# receiver_v0_1.net
KiCad netlist of a schematic drawn in Altium Designer
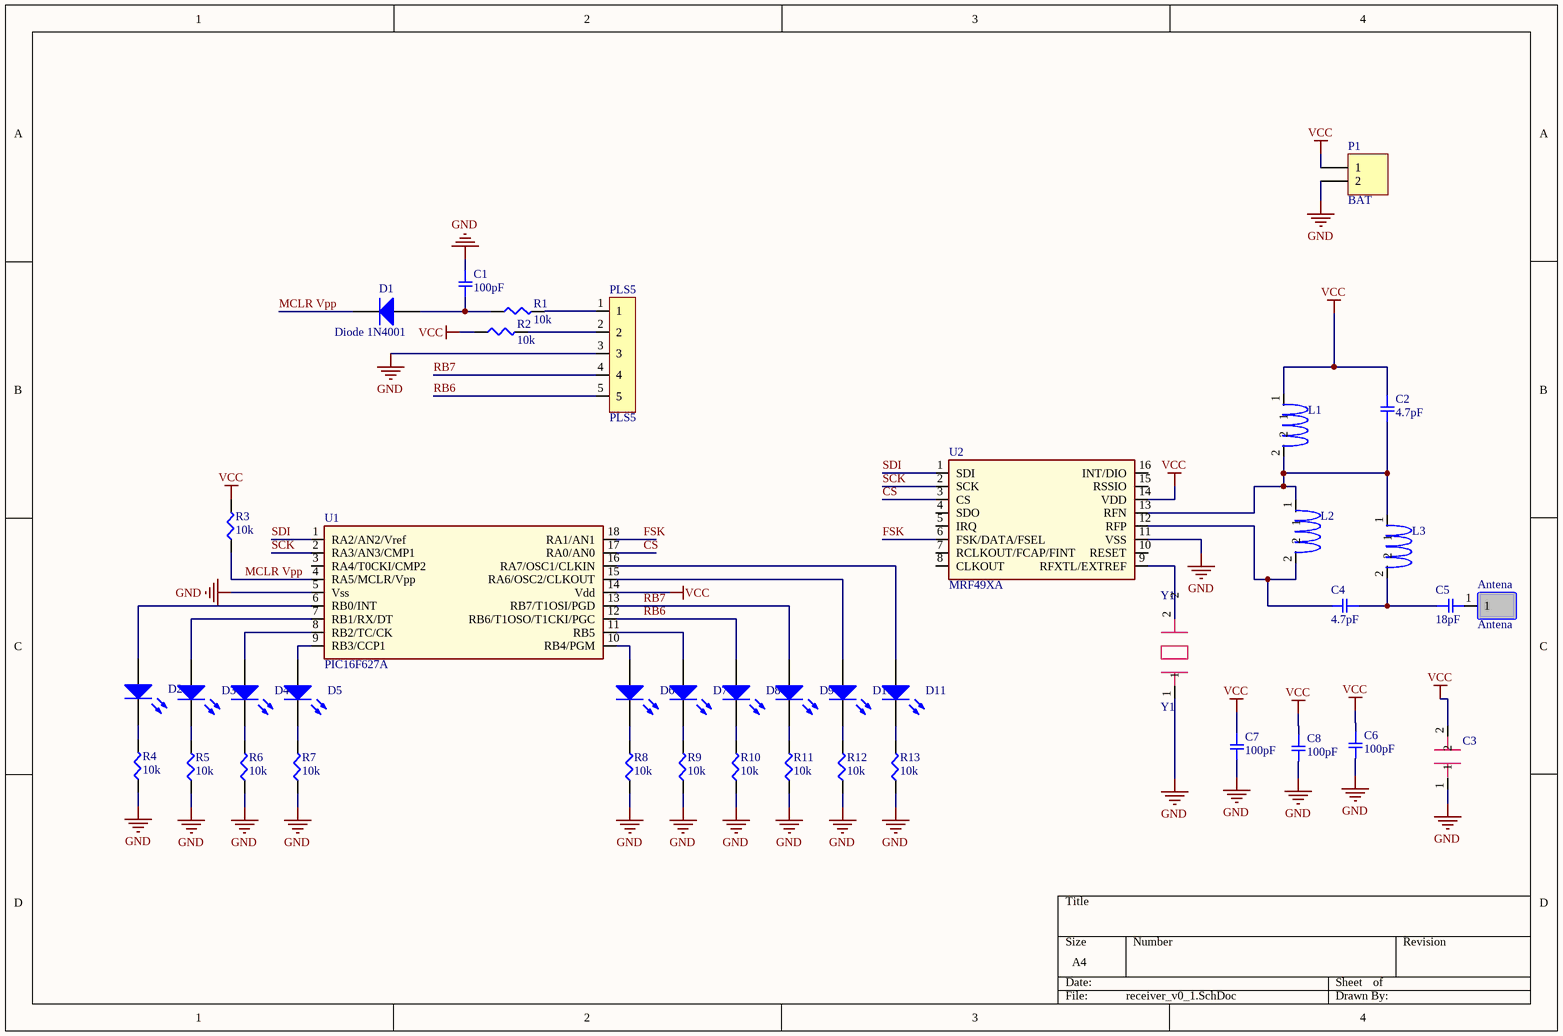
[diagram p0: receiver_v0_1.SchDoc]

(export (version "E")
  (design (tool "Eeschema 10.0.6"))
  (components
    (comp (ref "Antena") (value "Antena") (footprint "RCU:Anteny") (libsource (lib "RCU") (part "Antena")))
    (comp (ref "C1")
      (value "100pF")
      (footprint "SMD-1206C")
      (description "CAP CER 100PF 630V U2J 1206")
      (fields
        (field (name "DIGI-KEY PART NUMBER") "490-5043-1-ND")
        (field (name "PART NUMBER") "GCM31A7U2J101JX01D")
      )
      (libsource (lib "capacitor_murata_1206") (part "GCM31A7U2J101JX01D"))
    )
    (comp (ref "C2")
      (value "4.7pF")
      (footprint "SMD-0805C")
      (description "CAP CER 4.7PF 100V NP0 0805")
      (fields
        (field (name "DIGI-KEY PART NUMBER") "490-11278-1-ND")
        (field (name "PART NUMBER") "GQM2195C2A4R7BB01D")
      )
      (libsource (lib "capacitor_murata_0805") (part "GQM2195C2A4R7BB01D"))
    )
    (comp (ref "C3") (value "~") (footprint "RCU:С0805") (libsource (lib "RCU") (part "Capacity")))
    (comp (ref "C4")
      (value "4.7pF")
      (footprint "SMD-0805C")
      (description "CAP CER 4.7PF 100V NP0 0805")
      (fields
        (field (name "DIGI-KEY PART NUMBER") "490-11278-1-ND")
        (field (name "PART NUMBER") "GQM2195C2A4R7BB01D")
      )
      (libsource (lib "capacitor_murata_0805") (part "GQM2195C2A4R7BB01D"))
    )
    (comp (ref "C5")
      (value "18pF")
      (footprint "SMD-0805C")
      (description "CAP CER 18PF 100V NP0 0805")
      (fields
        (field (name "DIGI-KEY PART NUMBER") "490-3606-1-ND")
        (field (name "PART NUMBER") "GQM2195C2A180JB01D")
      )
      (libsource (lib "capacitor_murata_0805") (part "GQM2195C2A180JB01D"))
    )
    (comp (ref "C6")
      (value "100pF")
      (footprint "SMD-1206C")
      (description "CAP CER 100PF 630V U2J 1206")
      (fields
        (field (name "DIGI-KEY PART NUMBER") "490-5043-1-ND")
        (field (name "PART NUMBER") "GCM31A7U2J101JX01D")
      )
      (libsource (lib "capacitor_murata_1206") (part "GCM31A7U2J101JX01D"))
    )
    (comp (ref "C7")
      (value "100pF")
      (footprint "SMD-1206C")
      (description "CAP CER 100PF 630V U2J 1206")
      (fields
        (field (name "DIGI-KEY PART NUMBER") "490-5043-1-ND")
        (field (name "PART NUMBER") "GCM31A7U2J101JX01D")
      )
      (libsource (lib "capacitor_murata_1206") (part "GCM31A7U2J101JX01D"))
    )
    (comp (ref "C8")
      (value "100pF")
      (footprint "SMD-1206C")
      (description "CAP CER 100PF 630V U2J 1206")
      (fields
        (field (name "DIGI-KEY PART NUMBER") "490-5043-1-ND")
        (field (name "PART NUMBER") "GCM31A7U2J101JX01D")
      )
      (libsource (lib "capacitor_murata_1206") (part "GCM31A7U2J101JX01D"))
    )
    (comp (ref "D1")
      (value "Diode 1N4001")
      (footprint "DO-41")
      (description "1 Amp General Purpose Rectifier")
      (fields (field (name "PUBLISHER") "Altium Limited"))
      (libsource (lib "Miscellaneous Devices") (part "Diode 1N4001"))
    )
    (comp (ref "D2")
      (value "LED3")
      (footprint "3.5X2.8X1.9")
      (description "Typical BLUE SiC LED")
      (fields (field (name "PUBLISHER") "Altium Limited"))
      (libsource (lib "Miscellaneous Devices") (part "LED3"))
    )
    (comp (ref "D3")
      (value "LED3")
      (footprint "3.5X2.8X1.9")
      (description "Typical BLUE SiC LED")
      (fields (field (name "PUBLISHER") "Altium Limited"))
      (libsource (lib "Miscellaneous Devices") (part "LED3"))
    )
    (comp (ref "D4")
      (value "LED3")
      (footprint "3.5X2.8X1.9")
      (description "Typical BLUE SiC LED")
      (fields (field (name "PUBLISHER") "Altium Limited"))
      (libsource (lib "Miscellaneous Devices") (part "LED3"))
    )
    (comp (ref "D5")
      (value "LED3")
      (footprint "3.5X2.8X1.9")
      (description "Typical BLUE SiC LED")
      (fields (field (name "PUBLISHER") "Altium Limited"))
      (libsource (lib "Miscellaneous Devices") (part "LED3"))
    )
    (comp (ref "D6")
      (value "LED3")
      (footprint "3.5X2.8X1.9")
      (description "Typical BLUE SiC LED")
      (fields (field (name "PUBLISHER") "Altium Limited"))
      (libsource (lib "Miscellaneous Devices") (part "LED3"))
    )
    (comp (ref "D7")
      (value "LED3")
      (footprint "3.5X2.8X1.9")
      (description "Typical BLUE SiC LED")
      (fields (field (name "PUBLISHER") "Altium Limited"))
      (libsource (lib "Miscellaneous Devices") (part "LED3"))
    )
    (comp (ref "D8")
      (value "LED3")
      (footprint "3.5X2.8X1.9")
      (description "Typical BLUE SiC LED")
      (fields (field (name "PUBLISHER") "Altium Limited"))
      (libsource (lib "Miscellaneous Devices") (part "LED3"))
    )
    (comp (ref "D9")
      (value "LED3")
      (footprint "3.5X2.8X1.9")
      (description "Typical BLUE SiC LED")
      (fields (field (name "PUBLISHER") "Altium Limited"))
      (libsource (lib "Miscellaneous Devices") (part "LED3"))
    )
    (comp (ref "D10")
      (value "LED3")
      (footprint "3.5X2.8X1.9")
      (description "Typical BLUE SiC LED")
      (fields (field (name "PUBLISHER") "Altium Limited"))
      (libsource (lib "Miscellaneous Devices") (part "LED3"))
    )
    (comp (ref "D11")
      (value "LED3")
      (footprint "3.5X2.8X1.9")
      (description "Typical BLUE SiC LED")
      (fields (field (name "PUBLISHER") "Altium Limited"))
      (libsource (lib "Miscellaneous Devices") (part "LED3"))
    )
    (comp (ref "L1") (value "~") (footprint "RCU:L?") (libsource (lib "RCU") (part "Inductance")))
    (comp (ref "L2") (value "~") (footprint "RCU:L?") (libsource (lib "RCU") (part "Inductance")))
    (comp (ref "L3") (value "~") (footprint "RCU:L?") (libsource (lib "RCU") (part "Inductance")))
    (comp (ref "P1")
      (value "BAT")
      (footprint "HDR1X2")
      (description "Header, 2-Pin")
      (fields (field (name "PUBLISHER") "Altium Limited"))
      (libsource (lib "Miscellaneous Connectors") (part "Header 2"))
    )
    (comp (ref "PLS5") (value "PLS5") (footprint "RCU:PLS5") (libsource (lib "RCU") (part "PLS5")))
    (comp (ref "R1")
      (value "10k")
      (footprint "SMD-1206-RES")
      (description "RES SMD 10K OHM 5% 2/3W 1206")
      (fields (field (name "PART NUMBER") "ERJ-P08J103V") (field (name "DIGI-KEY PART NUMBER") "P10KALCT-ND"))
      (libsource (lib "Panasonic_ERJ_1206") (part "ERJ-P08J103V"))
    )
    (comp (ref "R2")
      (value "10k")
      (footprint "SMD-1206-RES")
      (description "RES SMD 10K OHM 5% 2/3W 1206")
      (fields (field (name "PART NUMBER") "ERJ-P08J103V") (field (name "DIGI-KEY PART NUMBER") "P10KALCT-ND"))
      (libsource (lib "Panasonic_ERJ_1206") (part "ERJ-P08J103V"))
    )
    (comp (ref "R3")
      (value "10k")
      (footprint "SMD-1206-RES")
      (description "RES SMD 10K OHM 5% 2/3W 1206")
      (fields (field (name "PART NUMBER") "ERJ-P08J103V") (field (name "DIGI-KEY PART NUMBER") "P10KALCT-ND"))
      (libsource (lib "Panasonic_ERJ_1206") (part "ERJ-P08J103V"))
    )
    (comp (ref "R4")
      (value "10k")
      (footprint "SMD-1206-RES")
      (description "RES SMD 10K OHM 5% 2/3W 1206")
      (fields (field (name "PART NUMBER") "ERJ-P08J103V") (field (name "DIGI-KEY PART NUMBER") "P10KALCT-ND"))
      (libsource (lib "Panasonic_ERJ_1206") (part "ERJ-P08J103V"))
    )
    (comp (ref "R5")
      (value "10k")
      (footprint "SMD-1206-RES")
      (description "RES SMD 10K OHM 5% 2/3W 1206")
      (fields (field (name "PART NUMBER") "ERJ-P08J103V") (field (name "DIGI-KEY PART NUMBER") "P10KALCT-ND"))
      (libsource (lib "Panasonic_ERJ_1206") (part "ERJ-P08J103V"))
    )
    (comp (ref "R6")
      (value "10k")
      (footprint "SMD-1206-RES")
      (description "RES SMD 10K OHM 5% 2/3W 1206")
      (fields (field (name "PART NUMBER") "ERJ-P08J103V") (field (name "DIGI-KEY PART NUMBER") "P10KALCT-ND"))
      (libsource (lib "Panasonic_ERJ_1206") (part "ERJ-P08J103V"))
    )
    (comp (ref "R7")
      (value "10k")
      (footprint "SMD-1206-RES")
      (description "RES SMD 10K OHM 5% 2/3W 1206")
      (fields (field (name "PART NUMBER") "ERJ-P08J103V") (field (name "DIGI-KEY PART NUMBER") "P10KALCT-ND"))
      (libsource (lib "Panasonic_ERJ_1206") (part "ERJ-P08J103V"))
    )
    (comp (ref "R8")
      (value "10k")
      (footprint "SMD-1206-RES")
      (description "RES SMD 10K OHM 5% 2/3W 1206")
      (fields (field (name "PART NUMBER") "ERJ-P08J103V") (field (name "DIGI-KEY PART NUMBER") "P10KALCT-ND"))
      (libsource (lib "Panasonic_ERJ_1206") (part "ERJ-P08J103V"))
    )
    (comp (ref "R9")
      (value "10k")
      (footprint "SMD-1206-RES")
      (description "RES SMD 10K OHM 5% 2/3W 1206")
      (fields (field (name "PART NUMBER") "ERJ-P08J103V") (field (name "DIGI-KEY PART NUMBER") "P10KALCT-ND"))
      (libsource (lib "Panasonic_ERJ_1206") (part "ERJ-P08J103V"))
    )
    (comp (ref "R10")
      (value "10k")
      (footprint "SMD-1206-RES")
      (description "RES SMD 10K OHM 5% 2/3W 1206")
      (fields (field (name "PART NUMBER") "ERJ-P08J103V") (field (name "DIGI-KEY PART NUMBER") "P10KALCT-ND"))
      (libsource (lib "Panasonic_ERJ_1206") (part "ERJ-P08J103V"))
    )
    (comp (ref "R11")
      (value "10k")
      (footprint "SMD-1206-RES")
      (description "RES SMD 10K OHM 5% 2/3W 1206")
      (fields (field (name "PART NUMBER") "ERJ-P08J103V") (field (name "DIGI-KEY PART NUMBER") "P10KALCT-ND"))
      (libsource (lib "Panasonic_ERJ_1206") (part "ERJ-P08J103V"))
    )
    (comp (ref "R12")
      (value "10k")
      (footprint "SMD-1206-RES")
      (description "RES SMD 10K OHM 5% 2/3W 1206")
      (fields (field (name "PART NUMBER") "ERJ-P08J103V") (field (name "DIGI-KEY PART NUMBER") "P10KALCT-ND"))
      (libsource (lib "Panasonic_ERJ_1206") (part "ERJ-P08J103V"))
    )
    (comp (ref "R13")
      (value "10k")
      (footprint "SMD-1206-RES")
      (description "RES SMD 10K OHM 5% 2/3W 1206")
      (fields (field (name "PART NUMBER") "ERJ-P08J103V") (field (name "DIGI-KEY PART NUMBER") "P10KALCT-ND"))
      (libsource (lib "Panasonic_ERJ_1206") (part "ERJ-P08J103V"))
    )
    (comp (ref "U1")
      (value "PIC16F627A")
      (footprint "RCU:PIC16F627A")
      (libsource (lib "RCU") (part "PIC16F627A"))
    )
    (comp (ref "U2") (value "MRF49XA") (footprint "RCU:MRF49XA") (libsource (lib "RCU") (part "MRF49XA")))
    (comp (ref "Y1") (value "Y1") (footprint "RCU:Quartz") (libsource (lib "RCU") (part "Quartz")))
  )
  (nets
    (net (code "1") (name "/CS") (class "Default")
      (node (ref "U1") (pin "17") (pinfunction "RA0/AN0_17") (pintype "passive"))
      (node (ref "U2") (pin "3") (pinfunction "CS_3") (pintype "passive"))
    )
    (net (code "2") (name "/FSK") (class "Default")
      (node (ref "U1") (pin "18") (pinfunction "RA1/AN1_18") (pintype "passive"))
      (node (ref "U2") (pin "6") (pinfunction "FSK/DATA/FSEL_6") (pintype "passive"))
    )
    (net (code "3") (name "/MCLR Vpp") (class "Default")
      (node (ref "D1") (pin "2") (pinfunction "K_2") (pintype "passive"))
      (node (ref "R3") (pin "1") (pinfunction "1_1") (pintype "passive"))
      (node (ref "U1") (pin "4") (pinfunction "RA5/MCLR/Vpp_4") (pintype "passive"))
    )
    (net (code "4") (name "/RB6") (class "Default")
      (node (ref "D8") (pin "1") (pinfunction "A_1") (pintype "passive"))
      (node (ref "PLS5") (pin "5") (pinfunction "5_5") (pintype "passive"))
      (node (ref "U1") (pin "12") (pinfunction "RB6/T1OSO/T1CKI/PGC_12") (pintype "passive"))
    )
    (net (code "5") (name "/RB7") (class "Default")
      (node (ref "D9") (pin "1") (pinfunction "A_1") (pintype "passive"))
      (node (ref "PLS5") (pin "4") (pinfunction "4_4") (pintype "passive"))
      (node (ref "U1") (pin "13") (pinfunction "RB7/T1OSI/PGD_13") (pintype "passive"))
    )
    (net (code "6") (name "/SCK") (class "Default")
      (node (ref "U1") (pin "2") (pinfunction "RA3/AN3/CMP1_2") (pintype "passive"))
      (node (ref "U2") (pin "2") (pinfunction "SCK_2") (pintype "passive"))
    )
    (net (code "7") (name "/SDI") (class "Default")
      (node (ref "U1") (pin "1") (pinfunction "RA2/AN2/Vref_1") (pintype "passive"))
      (node (ref "U2") (pin "1") (pinfunction "SDI_1") (pintype "passive"))
    )
    (net (code "8") (name "GND") (class "Default")
      (node (ref "C1") (pin "1") (pinfunction "1_1") (pintype "passive"))
      (node (ref "C3") (pin "1") (pinfunction "1_1") (pintype "passive"))
      (node (ref "C6") (pin "2") (pinfunction "2_2") (pintype "passive"))
      (node (ref "C7") (pin "2") (pinfunction "2_2") (pintype "passive"))
      (node (ref "C8") (pin "2") (pinfunction "2_2") (pintype "passive"))
      (node (ref "P1") (pin "2") (pinfunction "2_2") (pintype "passive"))
      (node (ref "PLS5") (pin "3") (pinfunction "3_3") (pintype "passive"))
      (node (ref "R10") (pin "1") (pinfunction "1_1") (pintype "passive"))
      (node (ref "R11") (pin "1") (pinfunction "1_1") (pintype "passive"))
      (node (ref "R12") (pin "1") (pinfunction "1_1") (pintype "passive"))
      (node (ref "R13") (pin "1") (pinfunction "1_1") (pintype "passive"))
      (node (ref "R4") (pin "1") (pinfunction "1_1") (pintype "passive"))
      (node (ref "R5") (pin "1") (pinfunction "1_1") (pintype "passive"))
      (node (ref "R6") (pin "1") (pinfunction "1_1") (pintype "passive"))
      (node (ref "R7") (pin "1") (pinfunction "1_1") (pintype "passive"))
      (node (ref "R8") (pin "1") (pinfunction "1_1") (pintype "passive"))
      (node (ref "R9") (pin "1") (pinfunction "1_1") (pintype "passive"))
      (node (ref "U1") (pin "5") (pinfunction "Vss_5") (pintype "passive"))
      (node (ref "U2") (pin "11") (pinfunction "VSS_11") (pintype "passive"))
      (node (ref "Y1") (pin "1") (pinfunction "1_1") (pintype "passive"))
    )
    (net (code "9") (name "Net-(Antena-Pad1)") (class "Default")
      (node (ref "Antena") (pin "1") (pinfunction "1_1") (pintype "passive"))
      (node (ref "C5") (pin "2") (pinfunction "2_2") (pintype "passive"))
    )
    (net (code "10") (name "Net-(C4-Pad1)") (class "Default")
      (node (ref "C4") (pin "1") (pinfunction "1_1") (pintype "passive"))
      (node (ref "C5") (pin "1") (pinfunction "1_1") (pintype "passive"))
      (node (ref "L3") (pin "2") (pinfunction "2_2") (pintype "passive"))
    )
    (net (code "11") (name "Net-(D1-A)") (class "Default")
      (node (ref "C1") (pin "2") (pinfunction "2_2") (pintype "passive"))
      (node (ref "D1") (pin "1") (pinfunction "A_1") (pintype "passive"))
      (node (ref "R1") (pin "1") (pinfunction "1_1") (pintype "passive"))
    )
    (net (code "12") (name "Net-(D2-A)") (class "Default")
      (node (ref "D2") (pin "1") (pinfunction "A_1") (pintype "passive"))
      (node (ref "U1") (pin "6") (pinfunction "RB0/INT_6") (pintype "passive"))
    )
    (net (code "13") (name "Net-(D2-K)") (class "Default")
      (node (ref "D2") (pin "2") (pinfunction "K_2") (pintype "passive"))
      (node (ref "R4") (pin "2") (pinfunction "2_2") (pintype "passive"))
    )
    (net (code "14") (name "Net-(D3-A)") (class "Default")
      (node (ref "D3") (pin "1") (pinfunction "A_1") (pintype "passive"))
      (node (ref "U1") (pin "7") (pinfunction "RB1/RX/DT_7") (pintype "passive"))
    )
    (net (code "15") (name "Net-(D3-K)") (class "Default")
      (node (ref "D3") (pin "2") (pinfunction "K_2") (pintype "passive"))
      (node (ref "R5") (pin "2") (pinfunction "2_2") (pintype "passive"))
    )
    (net (code "16") (name "Net-(D4-A)") (class "Default")
      (node (ref "D4") (pin "1") (pinfunction "A_1") (pintype "passive"))
      (node (ref "U1") (pin "8") (pinfunction "RB2/TC/CK_8") (pintype "passive"))
    )
    (net (code "17") (name "Net-(D4-K)") (class "Default")
      (node (ref "D4") (pin "2") (pinfunction "K_2") (pintype "passive"))
      (node (ref "R6") (pin "2") (pinfunction "2_2") (pintype "passive"))
    )
    (net (code "18") (name "Net-(D5-A)") (class "Default")
      (node (ref "D5") (pin "1") (pinfunction "A_1") (pintype "passive"))
      (node (ref "U1") (pin "9") (pinfunction "RB3/CCP1_9") (pintype "passive"))
    )
    (net (code "19") (name "Net-(D5-K)") (class "Default")
      (node (ref "D5") (pin "2") (pinfunction "K_2") (pintype "passive"))
      (node (ref "R7") (pin "2") (pinfunction "2_2") (pintype "passive"))
    )
    (net (code "20") (name "Net-(D6-A)") (class "Default")
      (node (ref "D6") (pin "1") (pinfunction "A_1") (pintype "passive"))
      (node (ref "U1") (pin "10") (pinfunction "RB4/PGM_10") (pintype "passive"))
    )
    (net (code "21") (name "Net-(D6-K)") (class "Default")
      (node (ref "D6") (pin "2") (pinfunction "K_2") (pintype "passive"))
      (node (ref "R8") (pin "2") (pinfunction "2_2") (pintype "passive"))
    )
    (net (code "22") (name "Net-(D7-A)") (class "Default")
      (node (ref "D7") (pin "1") (pinfunction "A_1") (pintype "passive"))
      (node (ref "U1") (pin "11") (pinfunction "RB5_11") (pintype "passive"))
    )
    (net (code "23") (name "Net-(D7-K)") (class "Default")
      (node (ref "D7") (pin "2") (pinfunction "K_2") (pintype "passive"))
      (node (ref "R9") (pin "2") (pinfunction "2_2") (pintype "passive"))
    )
    (net (code "24") (name "Net-(D8-K)") (class "Default")
      (node (ref "D8") (pin "2") (pinfunction "K_2") (pintype "passive"))
      (node (ref "R10") (pin "2") (pinfunction "2_2") (pintype "passive"))
    )
    (net (code "25") (name "Net-(D9-K)") (class "Default")
      (node (ref "D9") (pin "2") (pinfunction "K_2") (pintype "passive"))
      (node (ref "R11") (pin "2") (pinfunction "2_2") (pintype "passive"))
    )
    (net (code "26") (name "Net-(D10-A)") (class "Default")
      (node (ref "D10") (pin "1") (pinfunction "A_1") (pintype "passive"))
      (node (ref "U1") (pin "15") (pinfunction "RA6/OSC2/CLKOUT_15") (pintype "passive"))
    )
    (net (code "27") (name "Net-(D10-K)") (class "Default")
      (node (ref "D10") (pin "2") (pinfunction "K_2") (pintype "passive"))
      (node (ref "R12") (pin "2") (pinfunction "2_2") (pintype "passive"))
    )
    (net (code "28") (name "Net-(D11-A)") (class "Default")
      (node (ref "D11") (pin "1") (pinfunction "A_1") (pintype "passive"))
      (node (ref "U1") (pin "16") (pinfunction "RA7/OSC1/CLKIN_16") (pintype "passive"))
    )
    (net (code "29") (name "Net-(D11-K)") (class "Default")
      (node (ref "D11") (pin "2") (pinfunction "K_2") (pintype "passive"))
      (node (ref "R13") (pin "2") (pinfunction "2_2") (pintype "passive"))
    )
    (net (code "30") (name "Net-(PLS5-Pad1)") (class "Default")
      (node (ref "PLS5") (pin "1") (pinfunction "1_1") (pintype "passive"))
      (node (ref "R1") (pin "2") (pinfunction "2_2") (pintype "passive"))
    )
    (net (code "31") (name "Net-(PLS5-Pad2)") (class "Default")
      (node (ref "PLS5") (pin "2") (pinfunction "2_2") (pintype "passive"))
      (node (ref "R2") (pin "2") (pinfunction "2_2") (pintype "passive"))
    )
    (net (code "32") (name "Net-(U2-RFN)") (class "Default")
      (node (ref "C2") (pin "2") (pinfunction "2_2") (pintype "passive"))
      (node (ref "L1") (pin "2") (pinfunction "2_2") (pintype "passive"))
      (node (ref "L2") (pin "1") (pinfunction "1_1") (pintype "passive"))
      (node (ref "L3") (pin "1") (pinfunction "1_1") (pintype "passive"))
      (node (ref "U2") (pin "13") (pinfunction "RFN_13") (pintype "passive"))
    )
    (net (code "33") (name "Net-(U2-RFP)") (class "Default")
      (node (ref "C4") (pin "2") (pinfunction "2_2") (pintype "passive"))
      (node (ref "L2") (pin "2") (pinfunction "2_2") (pintype "passive"))
      (node (ref "U2") (pin "12") (pinfunction "RFP_12") (pintype "passive"))
    )
    (net (code "34") (name "Net-(U2-RFXTL{slash}EXTREF)") (class "Default")
      (node (ref "U2") (pin "9") (pinfunction "RFXTL/EXTREF_9") (pintype "passive"))
      (node (ref "Y1") (pin "2") (pinfunction "2_2") (pintype "passive"))
    )
    (net (code "35") (name "VCC") (class "Default")
      (node (ref "C2") (pin "1") (pinfunction "1_1") (pintype "passive"))
      (node (ref "C3") (pin "2") (pinfunction "2_2") (pintype "passive"))
      (node (ref "C6") (pin "1") (pinfunction "1_1") (pintype "passive"))
      (node (ref "C7") (pin "1") (pinfunction "1_1") (pintype "passive"))
      (node (ref "C8") (pin "1") (pinfunction "1_1") (pintype "passive"))
      (node (ref "L1") (pin "1") (pinfunction "1_1") (pintype "passive"))
      (node (ref "P1") (pin "1") (pinfunction "1_1") (pintype "passive"))
      (node (ref "R2") (pin "1") (pinfunction "1_1") (pintype "passive"))
      (node (ref "R3") (pin "2") (pinfunction "2_2") (pintype "passive"))
      (node (ref "U1") (pin "14") (pinfunction "Vdd_14") (pintype "passive"))
      (node (ref "U2") (pin "14") (pinfunction "VDD_14") (pintype "passive"))
    )
    (net (code "36") (name "unconnected-(U1-RA4{slash}T0CKI{slash}CMP2-Pad3)") (class "Default")
      (node (ref "U1") (pin "3") (pinfunction "RA4/T0CKI/CMP2_3") (pintype "passive"))
    )
    (net (code "37") (name "unconnected-(U2-CLKOUT-Pad8)") (class "Default")
      (node (ref "U2") (pin "8") (pinfunction "CLKOUT_8") (pintype "passive"))
    )
    (net (code "38") (name "unconnected-(U2-INT{slash}DIO-Pad16)") (class "Default")
      (node (ref "U2") (pin "16") (pinfunction "INT/DIO_16") (pintype "passive"))
    )
    (net (code "39") (name "unconnected-(U2-IRQ-Pad5)") (class "Default")
      (node (ref "U2") (pin "5") (pinfunction "IRQ_5") (pintype "passive"))
    )
    (net (code "40") (name "unconnected-(U2-RCLKOUT{slash}FCAP{slash}FINT-Pad7)") (class "Default")
      (node (ref "U2") (pin "7") (pinfunction "RCLKOUT/FCAP/FINT_7") (pintype "passive"))
    )
    (net (code "41") (name "unconnected-(U2-RESET-Pad10)") (class "Default")
      (node (ref "U2") (pin "10") (pinfunction "RESET_10") (pintype "passive"))
    )
    (net (code "42") (name "unconnected-(U2-RSSIO-Pad15)") (class "Default")
      (node (ref "U2") (pin "15") (pinfunction "RSSIO_15") (pintype "passive"))
    )
    (net (code "43") (name "unconnected-(U2-SDO-Pad4)") (class "Default")
      (node (ref "U2") (pin "4") (pinfunction "SDO_4") (pintype "passive"))
    )
  )
)
